# ATTiny10DevBrd.net
KiCad netlist of a schematic drawn in EAGLE
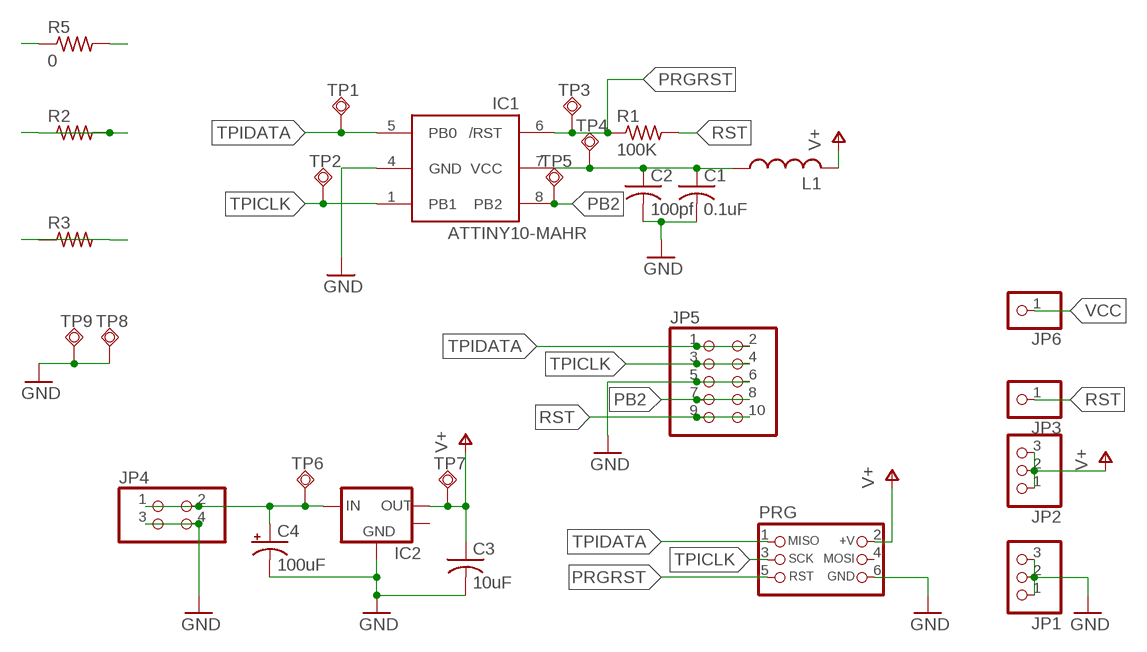
[diagram p0: schematic, sheet 1]

(export (version "E")
  (design (tool "Eeschema 10.0.6"))
  (components
    (comp (ref "C1")
      (value "0.1uF")
      (footprint "eagle-import:C0603")
      (libsource (lib "eagle-import") (part "adafruit_C-USC0603"))
    )
    (comp (ref "C2")
      (value "100pf")
      (footprint "eagle-import:C0402")
      (libsource (lib "eagle-import") (part "adafruit_C-USC0402"))
    )
    (comp (ref "C3")
      (value "10uF")
      (footprint "eagle-import:C0805K")
      (libsource (lib "eagle-import") (part "C-USC0805K"))
    )
    (comp (ref "C4")
      (value "100uF")
      (footprint "eagle-import:PANASONIC_E")
      (libsource (lib "eagle-import") (part "CPOL-USE"))
    )
    (comp (ref "IC1")
      (value "ATTINY10-MAHR")
      (footprint "eagle-import:UDFN-8")
      (libsource (lib "eagle-import") (part "ATTINY10-MAHR"))
    )
    (comp (ref "IC2")
      (value "V_REG_LM1117SOT223")
      (footprint "eagle-import:SOT223")
      (libsource (lib "eagle-import") (part "V_REG_LM1117SOT223"))
    )
    (comp (ref "JP1")
      (value "PINHD-1X3")
      (footprint "eagle-import:1X03")
      (libsource (lib "eagle-import") (part "PINHD-1X3"))
    )
    (comp (ref "JP2")
      (value "PINHD-1X3")
      (footprint "eagle-import:1X03")
      (libsource (lib "eagle-import") (part "PINHD-1X3"))
    )
    (comp (ref "JP3")
      (value "PINHD-1X1")
      (footprint "eagle-import:1X01")
      (libsource (lib "eagle-import") (part "PINHD-1X1"))
    )
    (comp (ref "JP4")
      (value "PINHD-2X2")
      (footprint "eagle-import:2X02")
      (libsource (lib "eagle-import") (part "PINHD-2X2"))
    )
    (comp (ref "JP5")
      (value "PINHD-2X5")
      (footprint "eagle-import:2X05")
      (libsource (lib "eagle-import") (part "PINHD-2X5"))
    )
    (comp (ref "JP6")
      (value "PINHD-1X1")
      (footprint "eagle-import:1X01")
      (libsource (lib "eagle-import") (part "PINHD-1X1"))
    )
    (comp (ref "L1")
      (value "L-USL1812")
      (footprint "eagle-import:L1812")
      (libsource (lib "eagle-import") (part "L-USL1812"))
    )
    (comp (ref "PRG")
      (value "CON_HEADER_PRG_AVR_ICSP_ETCH")
      (footprint "eagle-import:HEADER_PRG_2X03_ETCH")
      (libsource (lib "eagle-import") (part "CON_HEADER_PRG_AVR_ICSP_ETCH"))
    )
    (comp (ref "R1")
      (value "100K")
      (footprint "eagle-import:R0805")
      (libsource (lib "eagle-import") (part "R-US_R0805"))
    )
    (comp (ref "R2")
      (value "R-US_M1206")
      (footprint "eagle-import:M1206")
      (libsource (lib "eagle-import") (part "R-US_M1206"))
    )
    (comp (ref "R3")
      (value "R-US_M1206")
      (footprint "eagle-import:M1206")
      (libsource (lib "eagle-import") (part "R-US_M1206"))
    )
    (comp (ref "R5")
      (value "0")
      (footprint "eagle-import:M0805")
      (libsource (lib "eagle-import") (part "R-US_M0805"))
    )
    (comp (ref "TP1")
      (value "TPSQTP12R")
      (footprint "eagle-import:TP12R")
      (libsource (lib "eagle-import") (part "TPSQTP12R"))
    )
    (comp (ref "TP2")
      (value "TPSQTP12R")
      (footprint "eagle-import:TP12R")
      (libsource (lib "eagle-import") (part "TPSQTP12R"))
    )
    (comp (ref "TP3")
      (value "TPSQTP12R")
      (footprint "eagle-import:TP12R")
      (libsource (lib "eagle-import") (part "TPSQTP12R"))
    )
    (comp (ref "TP4")
      (value "TPSQTP12R")
      (footprint "eagle-import:TP12R")
      (libsource (lib "eagle-import") (part "TPSQTP12R"))
    )
    (comp (ref "TP5")
      (value "TPSQTP12R")
      (footprint "eagle-import:TP12R")
      (libsource (lib "eagle-import") (part "TPSQTP12R"))
    )
    (comp (ref "TP6")
      (value "TPSQTP12R")
      (footprint "eagle-import:TP12R")
      (libsource (lib "eagle-import") (part "TPSQTP12R"))
    )
    (comp (ref "TP7")
      (value "TPSQTP12R")
      (footprint "eagle-import:TP12R")
      (libsource (lib "eagle-import") (part "TPSQTP12R"))
    )
    (comp (ref "TP8")
      (value "TPSQTP12R")
      (footprint "eagle-import:TP12R")
      (libsource (lib "eagle-import") (part "TPSQTP12R"))
    )
    (comp (ref "TP9")
      (value "TPSQTP12R")
      (footprint "eagle-import:TP12R")
      (libsource (lib "eagle-import") (part "TPSQTP12R"))
    )
  )
  (nets
    (net (code "1") (name "/OUT") (class "Default")
      (node (ref "IC2") (pin "4") (pinfunction "OUT_4") (pintype "power_in"))
    )
    (net (code "2") (name "GND") (class "Default")
      (node (ref "C1") (pin "2") (pinfunction "2_2") (pintype "passive"))
      (node (ref "C2") (pin "2") (pinfunction "2_2") (pintype "passive"))
      (node (ref "C3") (pin "2") (pinfunction "2_2") (pintype "passive"))
      (node (ref "C4") (pin "-") (pinfunction "-_-") (pintype "passive"))
      (node (ref "IC1") (pin "4") (pinfunction "GND_4") (pintype "power_in"))
      (node (ref "IC2") (pin "1") (pinfunction "GND_1") (pintype "input"))
      (node (ref "JP1") (pin "1") (pinfunction "1_1") (pintype "passive"))
      (node (ref "JP1") (pin "2") (pinfunction "2_2") (pintype "passive"))
      (node (ref "JP1") (pin "3") (pinfunction "3_3") (pintype "passive"))
      (node (ref "JP4") (pin "3") (pinfunction "3_3") (pintype "passive"))
      (node (ref "JP4") (pin "4") (pinfunction "4_4") (pintype "passive"))
      (node (ref "JP5") (pin "5") (pinfunction "5_5") (pintype "passive"))
      (node (ref "JP5") (pin "6") (pinfunction "6_6") (pintype "passive"))
      (node (ref "PRG") (pin "6") (pinfunction "GND_6") (pintype "passive"))
      (node (ref "TP8") (pin "TP") (pinfunction "TP_TP") (pintype "input"))
      (node (ref "TP9") (pin "TP") (pinfunction "TP_TP") (pintype "input"))
    )
    (net (code "3") (name "Net-(IC2-IN)") (class "Default")
      (node (ref "C4") (pin "+") (pinfunction "+_+") (pintype "passive"))
      (node (ref "IC2") (pin "3") (pinfunction "IN_3") (pintype "input"))
      (node (ref "JP4") (pin "1") (pinfunction "1_1") (pintype "passive"))
      (node (ref "JP4") (pin "2") (pinfunction "2_2") (pintype "passive"))
      (node (ref "TP6") (pin "TP") (pinfunction "TP_TP") (pintype "input"))
    )
    (net (code "4") (name "PB2") (class "Default")
      (node (ref "IC1") (pin "8") (pinfunction "PB2_8") (pintype "bidirectional"))
      (node (ref "JP5") (pin "7") (pinfunction "7_7") (pintype "passive"))
      (node (ref "JP5") (pin "8") (pinfunction "8_8") (pintype "passive"))
      (node (ref "R3") (pin "1") (pinfunction "1_1") (pintype "passive"))
      (node (ref "R3") (pin "2") (pinfunction "2_2") (pintype "passive"))
      (node (ref "TP5") (pin "TP") (pinfunction "TP_TP") (pintype "input"))
    )
    (net (code "5") (name "PRGRST") (class "Default")
      (node (ref "IC1") (pin "6") (pinfunction "/RST_6") (pintype "bidirectional"))
      (node (ref "PRG") (pin "5") (pinfunction "RST_5") (pintype "passive"))
      (node (ref "R1") (pin "1") (pinfunction "1_1") (pintype "passive"))
      (node (ref "TP3") (pin "TP") (pinfunction "TP_TP") (pintype "input"))
    )
    (net (code "6") (name "RST") (class "Default")
      (node (ref "JP3") (pin "1") (pinfunction "1_1") (pintype "passive"))
      (node (ref "JP5") (pin "10") (pinfunction "10_10") (pintype "passive"))
      (node (ref "JP5") (pin "9") (pinfunction "9_9") (pintype "passive"))
      (node (ref "R1") (pin "2") (pinfunction "2_2") (pintype "passive"))
    )
    (net (code "7") (name "TPICLK") (class "Default")
      (node (ref "IC1") (pin "1") (pinfunction "PB1_1") (pintype "bidirectional"))
      (node (ref "JP5") (pin "3") (pinfunction "3_3") (pintype "passive"))
      (node (ref "JP5") (pin "4") (pinfunction "4_4") (pintype "passive"))
      (node (ref "PRG") (pin "3") (pinfunction "SCK_3") (pintype "passive"))
      (node (ref "R2") (pin "1") (pinfunction "1_1") (pintype "passive"))
      (node (ref "R2") (pin "2") (pinfunction "2_2") (pintype "passive"))
      (node (ref "TP2") (pin "TP") (pinfunction "TP_TP") (pintype "input"))
    )
    (net (code "8") (name "TPIDATA") (class "Default")
      (node (ref "IC1") (pin "5") (pinfunction "PB0_5") (pintype "bidirectional"))
      (node (ref "JP5") (pin "1") (pinfunction "1_1") (pintype "passive"))
      (node (ref "JP5") (pin "2") (pinfunction "2_2") (pintype "passive"))
      (node (ref "PRG") (pin "1") (pinfunction "MISO_1") (pintype "passive"))
      (node (ref "R5") (pin "1") (pinfunction "1_1") (pintype "passive"))
      (node (ref "R5") (pin "2") (pinfunction "2_2") (pintype "passive"))
      (node (ref "TP1") (pin "TP") (pinfunction "TP_TP") (pintype "input"))
    )
    (net (code "9") (name "V+") (class "Default")
      (node (ref "C3") (pin "1") (pinfunction "1_1") (pintype "passive"))
      (node (ref "IC2") (pin "2") (pinfunction "VR-OUTSM_2") (pintype "power_in"))
      (node (ref "JP2") (pin "1") (pinfunction "1_1") (pintype "passive"))
      (node (ref "JP2") (pin "2") (pinfunction "2_2") (pintype "passive"))
      (node (ref "JP2") (pin "3") (pinfunction "3_3") (pintype "passive"))
      (node (ref "L1") (pin "2") (pinfunction "2_2") (pintype "passive"))
      (node (ref "PRG") (pin "2") (pinfunction "+V_2") (pintype "passive"))
      (node (ref "TP7") (pin "TP") (pinfunction "TP_TP") (pintype "input"))
    )
    (net (code "10") (name "VCC") (class "Default")
      (node (ref "C1") (pin "1") (pinfunction "1_1") (pintype "passive"))
      (node (ref "C2") (pin "1") (pinfunction "1_1") (pintype "passive"))
      (node (ref "IC1") (pin "7") (pinfunction "VCC_7") (pintype "power_in"))
      (node (ref "JP6") (pin "1") (pinfunction "1_1") (pintype "passive"))
      (node (ref "L1") (pin "1") (pinfunction "1_1") (pintype "passive"))
      (node (ref "TP4") (pin "TP") (pinfunction "TP_TP") (pintype "input"))
    )
    (net (code "11") (name "unconnected-(PRG-MOSI-Pad4)") (class "Default")
      (node (ref "PRG") (pin "4") (pinfunction "MOSI_4") (pintype "passive"))
    )
  )
)
